# CONNECTOR.net
KiCad netlist of a schematic drawn in Altium Designer
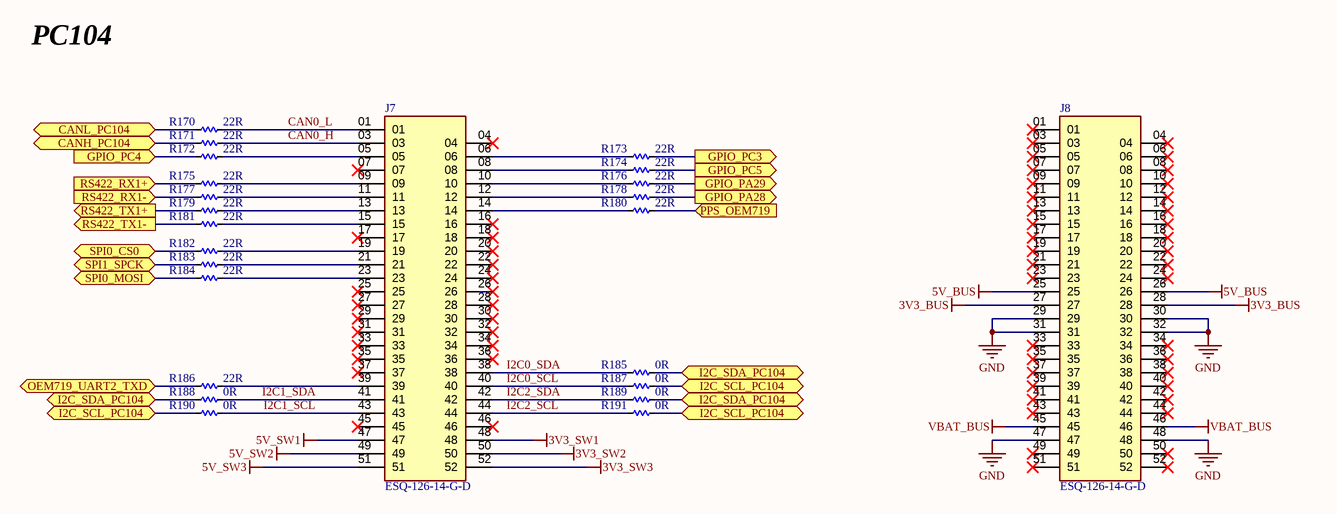
[diagram p0: CONNECTOR.SchDoc]

(export (version "E")
  (design (tool "Eeschema 10.0.6"))
  (components
    (comp (ref "J7")
      (value "ESQ-126-14-G-D")
      (footprint "ESQ-126-14-G-D")
      (description "PC / 104 Connectors Elevated Socket Strip")
      (libsource (lib "COMM_SCHLIB") (part "ESQ-126-14-G-D"))
    )
    (comp (ref "J8")
      (value "ESQ-126-14-G-D")
      (footprint "ESQ-126-14-G-D")
      (description "PC / 104 Connectors Elevated Socket Strip")
      (libsource (lib "COMM_SCHLIB") (part "ESQ-126-14-G-D"))
    )
    (comp (ref "R170")
      (value "22R")
      (footprint "RES_C_1608X60")
      (description "RES")
      (libsource (lib "LABLIB") (part "_RES_B_2"))
    )
    (comp (ref "R171")
      (value "22R")
      (footprint "RES_C_1608X60")
      (description "RES")
      (libsource (lib "LABLIB") (part "_RES_B_2"))
    )
    (comp (ref "R172")
      (value "22R")
      (footprint "RES_C_1608X60")
      (description "RES")
      (libsource (lib "LABLIB") (part "_RES_B_2"))
    )
    (comp (ref "R173")
      (value "22R")
      (footprint "RES_C_1608X60")
      (description "RES")
      (libsource (lib "LABLIB") (part "_RES_B_2"))
    )
    (comp (ref "R174")
      (value "22R")
      (footprint "RES_C_1608X60")
      (description "RES")
      (libsource (lib "LABLIB") (part "_RES_B_2"))
    )
    (comp (ref "R175")
      (value "22R")
      (footprint "RES_C_1608X60")
      (description "RES")
      (libsource (lib "LABLIB") (part "_RES_B_2"))
    )
    (comp (ref "R176")
      (value "22R")
      (footprint "RES_C_1608X60")
      (description "RES")
      (libsource (lib "LABLIB") (part "_RES_B_2"))
    )
    (comp (ref "R177")
      (value "22R")
      (footprint "RES_C_1608X60")
      (description "RES")
      (libsource (lib "LABLIB") (part "_RES_B_2"))
    )
    (comp (ref "R178")
      (value "22R")
      (footprint "RES_C_1608X60")
      (description "RES")
      (libsource (lib "LABLIB") (part "_RES_B_2"))
    )
    (comp (ref "R179")
      (value "22R")
      (footprint "RES_C_1608X60")
      (description "RES")
      (libsource (lib "LABLIB") (part "_RES_B_2"))
    )
    (comp (ref "R180")
      (value "22R")
      (footprint "RES_C_1608X60")
      (description "RES")
      (libsource (lib "LABLIB") (part "_RES_B_2"))
    )
    (comp (ref "R181")
      (value "22R")
      (footprint "RES_C_1608X60")
      (description "RES")
      (libsource (lib "LABLIB") (part "_RES_B_2"))
    )
    (comp (ref "R182")
      (value "22R")
      (footprint "RES_C_1608X60")
      (description "RES")
      (libsource (lib "LABLIB") (part "_RES_B_2"))
    )
    (comp (ref "R183")
      (value "22R")
      (footprint "RES_C_1608X60")
      (description "RES")
      (libsource (lib "LABLIB") (part "_RES_B_2"))
    )
    (comp (ref "R184")
      (value "22R")
      (footprint "RES_C_1608X60")
      (description "RES")
      (libsource (lib "LABLIB") (part "_RES_B_2"))
    )
    (comp (ref "R185")
      (value "0R")
      (footprint "RES_C_1608X60")
      (description "RES")
      (libsource (lib "LABLIB") (part "_RES_B_2"))
    )
    (comp (ref "R186")
      (value "22R")
      (footprint "RES_C_1608X60")
      (description "RES")
      (libsource (lib "LABLIB") (part "_RES_B_2"))
    )
    (comp (ref "R187")
      (value "0R")
      (footprint "RES_C_1608X60")
      (description "RES")
      (libsource (lib "LABLIB") (part "_RES_B_2"))
    )
    (comp (ref "R188")
      (value "0R")
      (footprint "RES_C_1608X60")
      (description "RES")
      (libsource (lib "LABLIB") (part "_RES_B_2"))
    )
    (comp (ref "R189")
      (value "0R")
      (footprint "RES_C_1608X60")
      (description "RES")
      (libsource (lib "LABLIB") (part "_RES_B_2"))
    )
    (comp (ref "R190")
      (value "0R")
      (footprint "RES_C_1608X60")
      (description "RES")
      (libsource (lib "LABLIB") (part "_RES_B_2"))
    )
    (comp (ref "R191")
      (value "0R")
      (footprint "RES_C_1608X60")
      (description "RES")
      (libsource (lib "LABLIB") (part "_RES_B_2"))
    )
  )
  (nets
    (net (code "1") (name "/CAN0_H") (class "Default")
      (node (ref "J7") (pin "03") (pinfunction "03_03") (pintype "passive"))
      (node (ref "R171") (pin "2") (pinfunction "2_2") (pintype "passive"))
    )
    (net (code "2") (name "/CAN0_L") (class "Default")
      (node (ref "J7") (pin "01") (pinfunction "01_01") (pintype "passive"))
      (node (ref "R170") (pin "2") (pinfunction "2_2") (pintype "passive"))
    )
    (net (code "3") (name "/CANH_PC104") (class "Default")
      (node (ref "R171") (pin "1") (pinfunction "1_1") (pintype "passive"))
    )
    (net (code "4") (name "/CANL_PC104") (class "Default")
      (node (ref "R170") (pin "1") (pinfunction "1_1") (pintype "passive"))
    )
    (net (code "5") (name "/GPIO_PA28") (class "Default")
      (node (ref "R178") (pin "2") (pinfunction "2_2") (pintype "passive"))
    )
    (net (code "6") (name "/GPIO_PA29") (class "Default")
      (node (ref "R176") (pin "2") (pinfunction "2_2") (pintype "passive"))
    )
    (net (code "7") (name "/GPIO_PC3") (class "Default")
      (node (ref "R173") (pin "2") (pinfunction "2_2") (pintype "passive"))
    )
    (net (code "8") (name "/GPIO_PC4") (class "Default")
      (node (ref "R172") (pin "1") (pinfunction "1_1") (pintype "passive"))
    )
    (net (code "9") (name "/GPIO_PC5") (class "Default")
      (node (ref "R174") (pin "2") (pinfunction "2_2") (pintype "passive"))
    )
    (net (code "10") (name "/I2C0_SCL") (class "Default")
      (node (ref "J7") (pin "40") (pinfunction "40_40") (pintype "passive"))
      (node (ref "R187") (pin "1") (pinfunction "1_1") (pintype "passive"))
    )
    (net (code "11") (name "/I2C0_SDA") (class "Default")
      (node (ref "J7") (pin "38") (pinfunction "38_38") (pintype "passive"))
      (node (ref "R185") (pin "1") (pinfunction "1_1") (pintype "passive"))
    )
    (net (code "12") (name "/I2C1_SCL") (class "Default")
      (node (ref "J7") (pin "43") (pinfunction "43_43") (pintype "passive"))
      (node (ref "R190") (pin "2") (pinfunction "2_2") (pintype "passive"))
    )
    (net (code "13") (name "/I2C1_SDA") (class "Default")
      (node (ref "J7") (pin "41") (pinfunction "41_41") (pintype "passive"))
      (node (ref "R188") (pin "2") (pinfunction "2_2") (pintype "passive"))
    )
    (net (code "14") (name "/I2C2_SCL") (class "Default")
      (node (ref "J7") (pin "44") (pinfunction "44_44") (pintype "passive"))
      (node (ref "R191") (pin "1") (pinfunction "1_1") (pintype "passive"))
    )
    (net (code "15") (name "/I2C2_SDA") (class "Default")
      (node (ref "J7") (pin "42") (pinfunction "42_42") (pintype "passive"))
      (node (ref "R189") (pin "1") (pinfunction "1_1") (pintype "passive"))
    )
    (net (code "16") (name "/I2C_SCL_PC104") (class "Default")
      (node (ref "R187") (pin "2") (pinfunction "2_2") (pintype "passive"))
      (node (ref "R190") (pin "1") (pinfunction "1_1") (pintype "passive"))
      (node (ref "R191") (pin "2") (pinfunction "2_2") (pintype "passive"))
    )
    (net (code "17") (name "/I2C_SDA_PC104") (class "Default")
      (node (ref "R185") (pin "2") (pinfunction "2_2") (pintype "passive"))
      (node (ref "R188") (pin "1") (pinfunction "1_1") (pintype "passive"))
      (node (ref "R189") (pin "2") (pinfunction "2_2") (pintype "passive"))
    )
    (net (code "18") (name "/OEM719_UART2_TXD") (class "Default")
      (node (ref "R186") (pin "1") (pinfunction "1_1") (pintype "passive"))
    )
    (net (code "19") (name "/PPS_OEM719") (class "Default")
      (node (ref "R180") (pin "2") (pinfunction "2_2") (pintype "passive"))
    )
    (net (code "20") (name "/RS422_RX1+") (class "Default")
      (node (ref "R175") (pin "1") (pinfunction "1_1") (pintype "passive"))
    )
    (net (code "21") (name "/RS422_RX1-") (class "Default")
      (node (ref "R177") (pin "1") (pinfunction "1_1") (pintype "passive"))
    )
    (net (code "22") (name "/RS422_TX1+") (class "Default")
      (node (ref "R179") (pin "1") (pinfunction "1_1") (pintype "passive"))
    )
    (net (code "23") (name "/RS422_TX1-") (class "Default")
      (node (ref "R181") (pin "1") (pinfunction "1_1") (pintype "passive"))
    )
    (net (code "24") (name "/SPI0_CS0") (class "Default")
      (node (ref "R182") (pin "1") (pinfunction "1_1") (pintype "passive"))
    )
    (net (code "25") (name "/SPI0_MOSI") (class "Default")
      (node (ref "R184") (pin "1") (pinfunction "1_1") (pintype "passive"))
    )
    (net (code "26") (name "/SPI1_SPCK") (class "Default")
      (node (ref "R183") (pin "1") (pinfunction "1_1") (pintype "passive"))
    )
    (net (code "27") (name "3V3_BUS") (class "Default")
      (node (ref "J8") (pin "27") (pinfunction "27_27") (pintype "passive"))
      (node (ref "J8") (pin "28") (pinfunction "28_28") (pintype "passive"))
    )
    (net (code "28") (name "3V3_SW1") (class "Default")
      (node (ref "J7") (pin "48") (pinfunction "48_48") (pintype "passive"))
    )
    (net (code "29") (name "3V3_SW2") (class "Default")
      (node (ref "J7") (pin "50") (pinfunction "50_50") (pintype "passive"))
    )
    (net (code "30") (name "3V3_SW3") (class "Default")
      (node (ref "J7") (pin "52") (pinfunction "52_52") (pintype "passive"))
    )
    (net (code "31") (name "5V_BUS") (class "Default")
      (node (ref "J8") (pin "25") (pinfunction "25_25") (pintype "passive"))
      (node (ref "J8") (pin "26") (pinfunction "26_26") (pintype "passive"))
    )
    (net (code "32") (name "5V_SW1") (class "Default")
      (node (ref "J7") (pin "47") (pinfunction "47_47") (pintype "passive"))
    )
    (net (code "33") (name "5V_SW2") (class "Default")
      (node (ref "J7") (pin "49") (pinfunction "49_49") (pintype "passive"))
    )
    (net (code "34") (name "5V_SW3") (class "Default")
      (node (ref "J7") (pin "51") (pinfunction "51_51") (pintype "passive"))
    )
    (net (code "35") (name "GND") (class "Default")
      (node (ref "J8") (pin "29") (pinfunction "29_29") (pintype "passive"))
      (node (ref "J8") (pin "30") (pinfunction "30_30") (pintype "passive"))
      (node (ref "J8") (pin "31") (pinfunction "31_31") (pintype "passive"))
      (node (ref "J8") (pin "32") (pinfunction "32_32") (pintype "passive"))
      (node (ref "J8") (pin "47") (pinfunction "47_47") (pintype "passive"))
      (node (ref "J8") (pin "48") (pinfunction "48_48") (pintype "passive"))
    )
    (net (code "36") (name "Net-(J7-Pad05)") (class "Default")
      (node (ref "J7") (pin "05") (pinfunction "05_05") (pintype "passive"))
      (node (ref "R172") (pin "2") (pinfunction "2_2") (pintype "passive"))
    )
    (net (code "37") (name "Net-(J7-Pad06)") (class "Default")
      (node (ref "J7") (pin "06") (pinfunction "06_06") (pintype "passive"))
      (node (ref "R173") (pin "1") (pinfunction "1_1") (pintype "passive"))
    )
    (net (code "38") (name "Net-(J7-Pad08)") (class "Default")
      (node (ref "J7") (pin "08") (pinfunction "08_08") (pintype "passive"))
      (node (ref "R174") (pin "1") (pinfunction "1_1") (pintype "passive"))
    )
    (net (code "39") (name "Net-(J7-Pad09)") (class "Default")
      (node (ref "J7") (pin "09") (pinfunction "09_09") (pintype "passive"))
      (node (ref "R175") (pin "2") (pinfunction "2_2") (pintype "passive"))
    )
    (net (code "40") (name "Net-(J7-Pad10)") (class "Default")
      (node (ref "J7") (pin "10") (pinfunction "10_10") (pintype "passive"))
      (node (ref "R176") (pin "1") (pinfunction "1_1") (pintype "passive"))
    )
    (net (code "41") (name "Net-(J7-Pad11)") (class "Default")
      (node (ref "J7") (pin "11") (pinfunction "11_11") (pintype "passive"))
      (node (ref "R177") (pin "2") (pinfunction "2_2") (pintype "passive"))
    )
    (net (code "42") (name "Net-(J7-Pad12)") (class "Default")
      (node (ref "J7") (pin "12") (pinfunction "12_12") (pintype "passive"))
      (node (ref "R178") (pin "1") (pinfunction "1_1") (pintype "passive"))
    )
    (net (code "43") (name "Net-(J7-Pad13)") (class "Default")
      (node (ref "J7") (pin "13") (pinfunction "13_13") (pintype "passive"))
      (node (ref "R179") (pin "2") (pinfunction "2_2") (pintype "passive"))
    )
    (net (code "44") (name "Net-(J7-Pad14)") (class "Default")
      (node (ref "J7") (pin "14") (pinfunction "14_14") (pintype "passive"))
      (node (ref "R180") (pin "1") (pinfunction "1_1") (pintype "passive"))
    )
    (net (code "45") (name "Net-(J7-Pad15)") (class "Default")
      (node (ref "J7") (pin "15") (pinfunction "15_15") (pintype "passive"))
      (node (ref "R181") (pin "2") (pinfunction "2_2") (pintype "passive"))
    )
    (net (code "46") (name "Net-(J7-Pad19)") (class "Default")
      (node (ref "J7") (pin "19") (pinfunction "19_19") (pintype "passive"))
      (node (ref "R182") (pin "2") (pinfunction "2_2") (pintype "passive"))
    )
    (net (code "47") (name "Net-(J7-Pad21)") (class "Default")
      (node (ref "J7") (pin "21") (pinfunction "21_21") (pintype "passive"))
      (node (ref "R183") (pin "2") (pinfunction "2_2") (pintype "passive"))
    )
    (net (code "48") (name "Net-(J7-Pad23)") (class "Default")
      (node (ref "J7") (pin "23") (pinfunction "23_23") (pintype "passive"))
      (node (ref "R184") (pin "2") (pinfunction "2_2") (pintype "passive"))
    )
    (net (code "49") (name "Net-(J7-Pad39)") (class "Default")
      (node (ref "J7") (pin "39") (pinfunction "39_39") (pintype "passive"))
      (node (ref "R186") (pin "2") (pinfunction "2_2") (pintype "passive"))
    )
    (net (code "50") (name "VBAT_BUS") (class "Default")
      (node (ref "J8") (pin "45") (pinfunction "45_45") (pintype "passive"))
      (node (ref "J8") (pin "46") (pinfunction "46_46") (pintype "passive"))
    )
    (net (code "51") (name "unconnected-(J7-Pad04)") (class "Default")
      (node (ref "J7") (pin "04") (pinfunction "04_04") (pintype "passive+no_connect"))
    )
    (net (code "52") (name "unconnected-(J7-Pad07)") (class "Default")
      (node (ref "J7") (pin "07") (pinfunction "07_07") (pintype "passive+no_connect"))
    )
    (net (code "53") (name "unconnected-(J7-Pad16)") (class "Default")
      (node (ref "J7") (pin "16") (pinfunction "16_16") (pintype "passive+no_connect"))
    )
    (net (code "54") (name "unconnected-(J7-Pad17)") (class "Default")
      (node (ref "J7") (pin "17") (pinfunction "17_17") (pintype "passive+no_connect"))
    )
    (net (code "55") (name "unconnected-(J7-Pad18)") (class "Default")
      (node (ref "J7") (pin "18") (pinfunction "18_18") (pintype "passive+no_connect"))
    )
    (net (code "56") (name "unconnected-(J7-Pad20)") (class "Default")
      (node (ref "J7") (pin "20") (pinfunction "20_20") (pintype "passive+no_connect"))
    )
    (net (code "57") (name "unconnected-(J7-Pad22)") (class "Default")
      (node (ref "J7") (pin "22") (pinfunction "22_22") (pintype "passive+no_connect"))
    )
    (net (code "58") (name "unconnected-(J7-Pad24)") (class "Default")
      (node (ref "J7") (pin "24") (pinfunction "24_24") (pintype "passive+no_connect"))
    )
    (net (code "59") (name "unconnected-(J7-Pad25)") (class "Default")
      (node (ref "J7") (pin "25") (pinfunction "25_25") (pintype "passive+no_connect"))
    )
    (net (code "60") (name "unconnected-(J7-Pad26)") (class "Default")
      (node (ref "J7") (pin "26") (pinfunction "26_26") (pintype "passive+no_connect"))
    )
    (net (code "61") (name "unconnected-(J7-Pad27)") (class "Default")
      (node (ref "J7") (pin "27") (pinfunction "27_27") (pintype "passive+no_connect"))
    )
    (net (code "62") (name "unconnected-(J7-Pad28)") (class "Default")
      (node (ref "J7") (pin "28") (pinfunction "28_28") (pintype "passive+no_connect"))
    )
    (net (code "63") (name "unconnected-(J7-Pad29)") (class "Default")
      (node (ref "J7") (pin "29") (pinfunction "29_29") (pintype "passive+no_connect"))
    )
    (net (code "64") (name "unconnected-(J7-Pad30)") (class "Default")
      (node (ref "J7") (pin "30") (pinfunction "30_30") (pintype "passive+no_connect"))
    )
    (net (code "65") (name "unconnected-(J7-Pad31)") (class "Default")
      (node (ref "J7") (pin "31") (pinfunction "31_31") (pintype "passive+no_connect"))
    )
    (net (code "66") (name "unconnected-(J7-Pad32)") (class "Default")
      (node (ref "J7") (pin "32") (pinfunction "32_32") (pintype "passive+no_connect"))
    )
    (net (code "67") (name "unconnected-(J7-Pad33)") (class "Default")
      (node (ref "J7") (pin "33") (pinfunction "33_33") (pintype "passive+no_connect"))
    )
    (net (code "68") (name "unconnected-(J7-Pad34)") (class "Default")
      (node (ref "J7") (pin "34") (pinfunction "34_34") (pintype "passive+no_connect"))
    )
    (net (code "69") (name "unconnected-(J7-Pad35)") (class "Default")
      (node (ref "J7") (pin "35") (pinfunction "35_35") (pintype "passive+no_connect"))
    )
    (net (code "70") (name "unconnected-(J7-Pad36)") (class "Default")
      (node (ref "J7") (pin "36") (pinfunction "36_36") (pintype "passive+no_connect"))
    )
    (net (code "71") (name "unconnected-(J7-Pad37)") (class "Default")
      (node (ref "J7") (pin "37") (pinfunction "37_37") (pintype "passive+no_connect"))
    )
    (net (code "72") (name "unconnected-(J7-Pad45)") (class "Default")
      (node (ref "J7") (pin "45") (pinfunction "45_45") (pintype "passive+no_connect"))
    )
    (net (code "73") (name "unconnected-(J7-Pad46)") (class "Default")
      (node (ref "J7") (pin "46") (pinfunction "46_46") (pintype "passive+no_connect"))
    )
    (net (code "74") (name "unconnected-(J8-Pad01)") (class "Default")
      (node (ref "J8") (pin "01") (pinfunction "01_01") (pintype "passive+no_connect"))
    )
    (net (code "75") (name "unconnected-(J8-Pad03)") (class "Default")
      (node (ref "J8") (pin "03") (pinfunction "03_03") (pintype "passive+no_connect"))
    )
    (net (code "76") (name "unconnected-(J8-Pad04)") (class "Default")
      (node (ref "J8") (pin "04") (pinfunction "04_04") (pintype "passive+no_connect"))
    )
    (net (code "77") (name "unconnected-(J8-Pad05)") (class "Default")
      (node (ref "J8") (pin "05") (pinfunction "05_05") (pintype "passive+no_connect"))
    )
    (net (code "78") (name "unconnected-(J8-Pad06)") (class "Default")
      (node (ref "J8") (pin "06") (pinfunction "06_06") (pintype "passive+no_connect"))
    )
    (net (code "79") (name "unconnected-(J8-Pad07)") (class "Default")
      (node (ref "J8") (pin "07") (pinfunction "07_07") (pintype "passive+no_connect"))
    )
    (net (code "80") (name "unconnected-(J8-Pad08)") (class "Default")
      (node (ref "J8") (pin "08") (pinfunction "08_08") (pintype "passive+no_connect"))
    )
    (net (code "81") (name "unconnected-(J8-Pad09)") (class "Default")
      (node (ref "J8") (pin "09") (pinfunction "09_09") (pintype "passive+no_connect"))
    )
    (net (code "82") (name "unconnected-(J8-Pad10)") (class "Default")
      (node (ref "J8") (pin "10") (pinfunction "10_10") (pintype "passive+no_connect"))
    )
    (net (code "83") (name "unconnected-(J8-Pad11)") (class "Default")
      (node (ref "J8") (pin "11") (pinfunction "11_11") (pintype "passive+no_connect"))
    )
    (net (code "84") (name "unconnected-(J8-Pad12)") (class "Default")
      (node (ref "J8") (pin "12") (pinfunction "12_12") (pintype "passive+no_connect"))
    )
    (net (code "85") (name "unconnected-(J8-Pad13)") (class "Default")
      (node (ref "J8") (pin "13") (pinfunction "13_13") (pintype "passive+no_connect"))
    )
    (net (code "86") (name "unconnected-(J8-Pad14)") (class "Default")
      (node (ref "J8") (pin "14") (pinfunction "14_14") (pintype "passive+no_connect"))
    )
    (net (code "87") (name "unconnected-(J8-Pad15)") (class "Default")
      (node (ref "J8") (pin "15") (pinfunction "15_15") (pintype "passive+no_connect"))
    )
    (net (code "88") (name "unconnected-(J8-Pad16)") (class "Default")
      (node (ref "J8") (pin "16") (pinfunction "16_16") (pintype "passive+no_connect"))
    )
    (net (code "89") (name "unconnected-(J8-Pad17)") (class "Default")
      (node (ref "J8") (pin "17") (pinfunction "17_17") (pintype "passive+no_connect"))
    )
    (net (code "90") (name "unconnected-(J8-Pad18)") (class "Default")
      (node (ref "J8") (pin "18") (pinfunction "18_18") (pintype "passive+no_connect"))
    )
    (net (code "91") (name "unconnected-(J8-Pad19)") (class "Default")
      (node (ref "J8") (pin "19") (pinfunction "19_19") (pintype "passive+no_connect"))
    )
    (net (code "92") (name "unconnected-(J8-Pad20)") (class "Default")
      (node (ref "J8") (pin "20") (pinfunction "20_20") (pintype "passive+no_connect"))
    )
    (net (code "93") (name "unconnected-(J8-Pad21)") (class "Default")
      (node (ref "J8") (pin "21") (pinfunction "21_21") (pintype "passive+no_connect"))
    )
    (net (code "94") (name "unconnected-(J8-Pad22)") (class "Default")
      (node (ref "J8") (pin "22") (pinfunction "22_22") (pintype "passive+no_connect"))
    )
    (net (code "95") (name "unconnected-(J8-Pad23)") (class "Default")
      (node (ref "J8") (pin "23") (pinfunction "23_23") (pintype "passive+no_connect"))
    )
    (net (code "96") (name "unconnected-(J8-Pad24)") (class "Default")
      (node (ref "J8") (pin "24") (pinfunction "24_24") (pintype "passive+no_connect"))
    )
    (net (code "97") (name "unconnected-(J8-Pad33)") (class "Default")
      (node (ref "J8") (pin "33") (pinfunction "33_33") (pintype "passive+no_connect"))
    )
    (net (code "98") (name "unconnected-(J8-Pad34)") (class "Default")
      (node (ref "J8") (pin "34") (pinfunction "34_34") (pintype "passive+no_connect"))
    )
    (net (code "99") (name "unconnected-(J8-Pad35)") (class "Default")
      (node (ref "J8") (pin "35") (pinfunction "35_35") (pintype "passive+no_connect"))
    )
    (net (code "100") (name "unconnected-(J8-Pad36)") (class "Default")
      (node (ref "J8") (pin "36") (pinfunction "36_36") (pintype "passive+no_connect"))
    )
    (net (code "101") (name "unconnected-(J8-Pad37)") (class "Default")
      (node (ref "J8") (pin "37") (pinfunction "37_37") (pintype "passive+no_connect"))
    )
    (net (code "102") (name "unconnected-(J8-Pad38)") (class "Default")
      (node (ref "J8") (pin "38") (pinfunction "38_38") (pintype "passive+no_connect"))
    )
    (net (code "103") (name "unconnected-(J8-Pad39)") (class "Default")
      (node (ref "J8") (pin "39") (pinfunction "39_39") (pintype "passive+no_connect"))
    )
    (net (code "104") (name "unconnected-(J8-Pad40)") (class "Default")
      (node (ref "J8") (pin "40") (pinfunction "40_40") (pintype "passive+no_connect"))
    )
    (net (code "105") (name "unconnected-(J8-Pad41)") (class "Default")
      (node (ref "J8") (pin "41") (pinfunction "41_41") (pintype "passive+no_connect"))
    )
    (net (code "106") (name "unconnected-(J8-Pad42)") (class "Default")
      (node (ref "J8") (pin "42") (pinfunction "42_42") (pintype "passive+no_connect"))
    )
    (net (code "107") (name "unconnected-(J8-Pad43)") (class "Default")
      (node (ref "J8") (pin "43") (pinfunction "43_43") (pintype "passive+no_connect"))
    )
    (net (code "108") (name "unconnected-(J8-Pad44)") (class "Default")
      (node (ref "J8") (pin "44") (pinfunction "44_44") (pintype "passive+no_connect"))
    )
    (net (code "109") (name "unconnected-(J8-Pad49)") (class "Default")
      (node (ref "J8") (pin "49") (pinfunction "49_49") (pintype "passive+no_connect"))
    )
    (net (code "110") (name "unconnected-(J8-Pad50)") (class "Default")
      (node (ref "J8") (pin "50") (pinfunction "50_50") (pintype "passive+no_connect"))
    )
    (net (code "111") (name "unconnected-(J8-Pad51)") (class "Default")
      (node (ref "J8") (pin "51") (pinfunction "51_51") (pintype "passive+no_connect"))
    )
    (net (code "112") (name "unconnected-(J8-Pad52)") (class "Default")
      (node (ref "J8") (pin "52") (pinfunction "52_52") (pintype "passive+no_connect"))
    )
  )
)
